# axiom_beta_smart_power_adapter_v0_1_r1_1.net
KiCad netlist of a schematic drawn in EAGLE
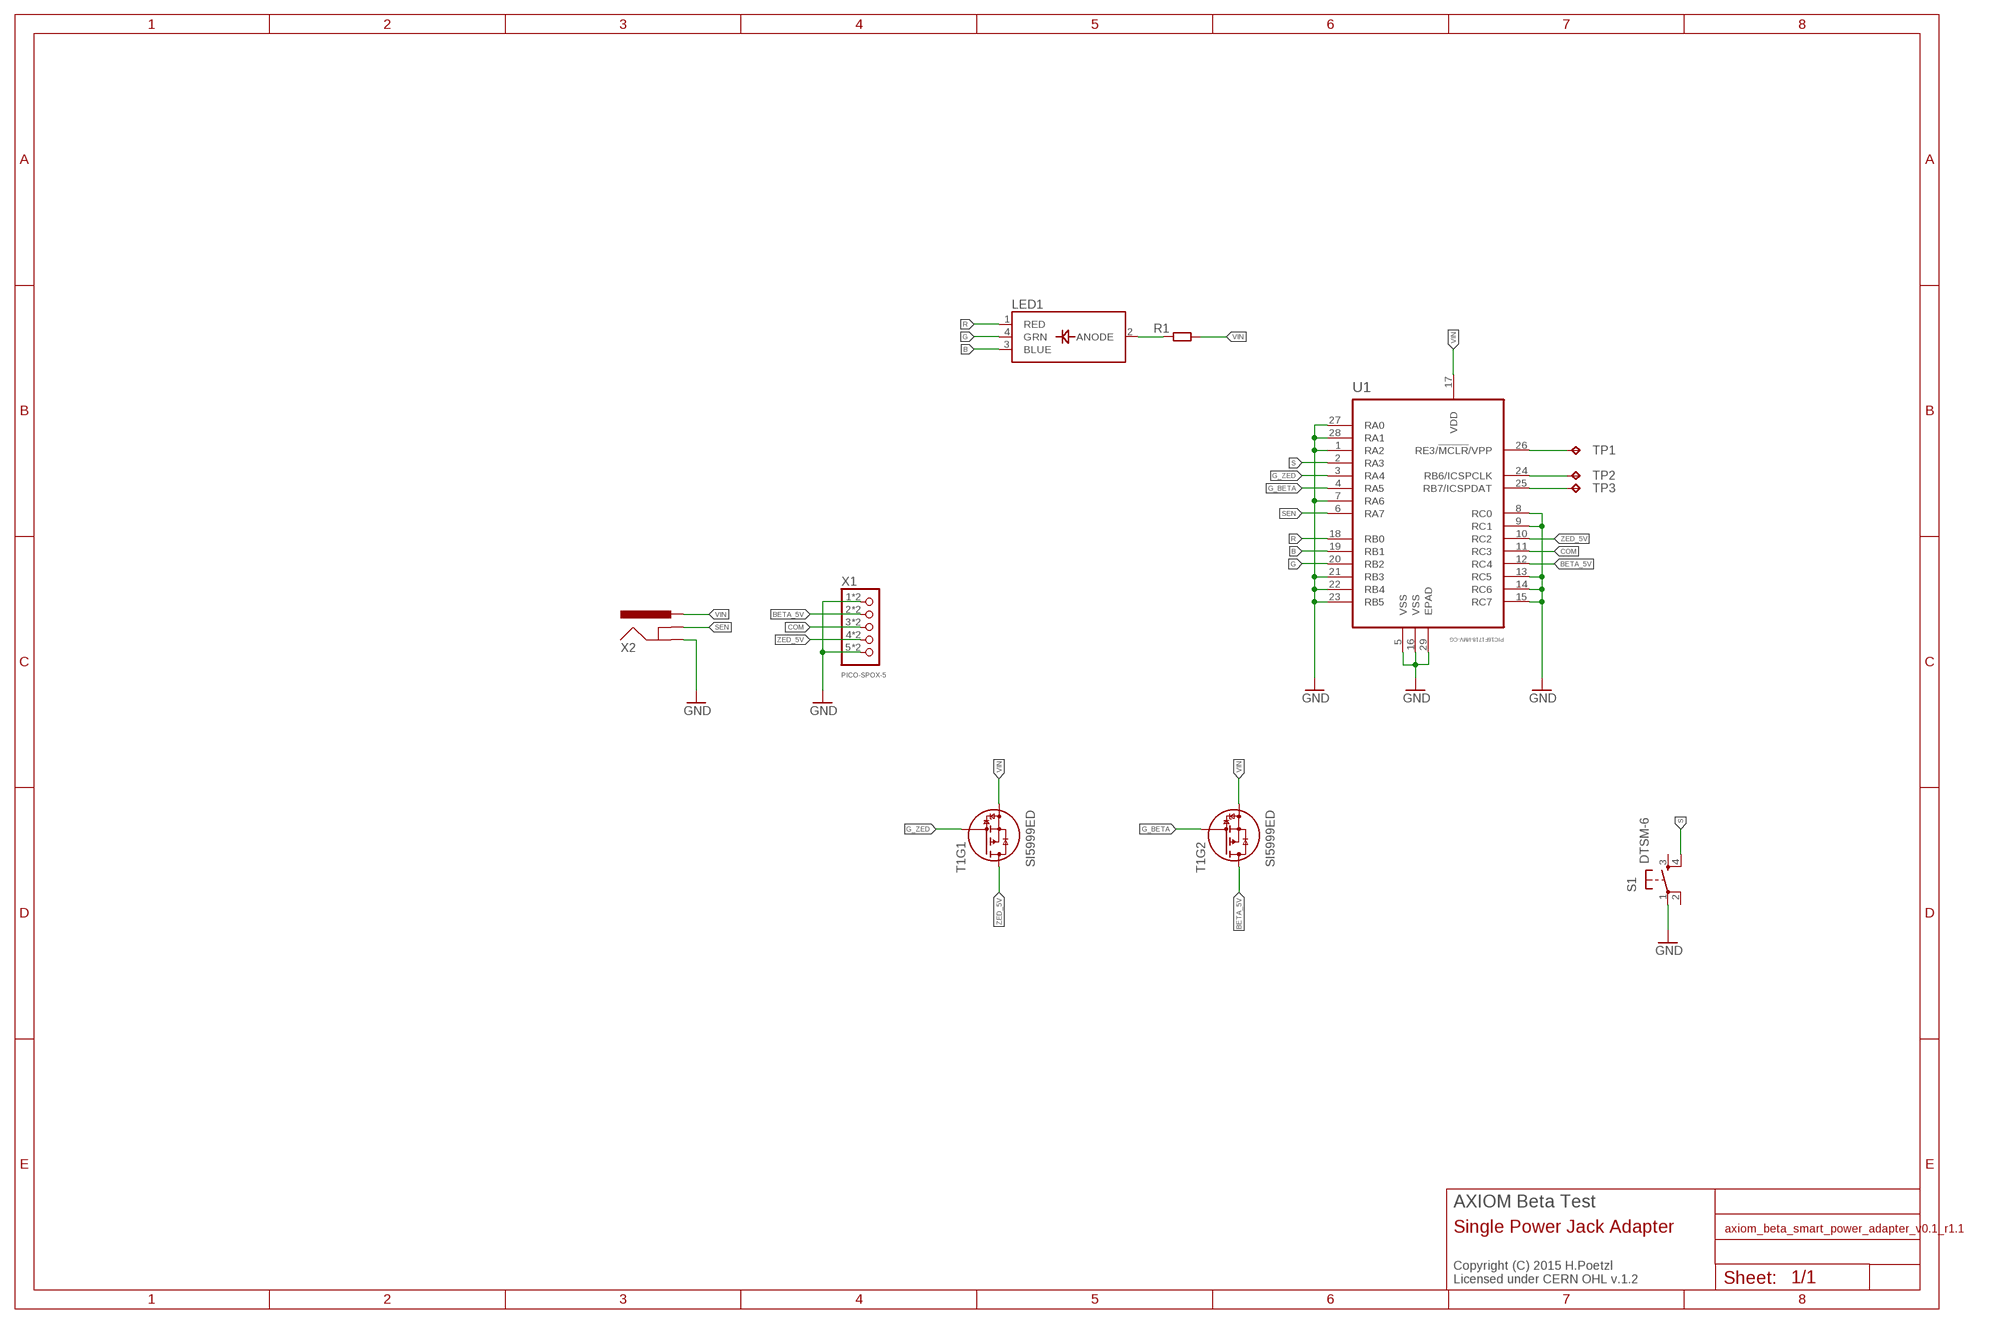
[diagram p0: schematic, sheet 1]

(export (version "E")
  (design (tool "Eeschema 10.0.6"))
  (components
    (comp (ref "LED1")
      (value "LED_RGB_PLCC4")
      (footprint "eagle-import:RGBLED_PLCC4")
      (libsource (lib "eagle-import") (part "LED_RGB_PLCC4"))
    )
    (comp (ref "R1")
      (value "R0402-C")
      (footprint "eagle-import:0402-C")
      (libsource (lib "eagle-import") (part "R0402-C"))
    )
    (comp (ref "S1")
      (value "DTSM-6")
      (footprint "eagle-import:3X4MM")
      (libsource (lib "eagle-import") (part "DTSM-6"))
    )
    (comp (ref "T1")
      (value "SI5999ED")
      (footprint "eagle-import:PPAK-CHIPFET-DUAL")
      (libsource (lib "eagle-import") (part "SI5999ED"))
    )
    (comp (ref "TP1")
      (value "TPTP07R")
      (footprint "eagle-import:TP07R")
      (libsource (lib "eagle-import") (part "TPTP07R"))
    )
    (comp (ref "TP2")
      (value "TPTP07R")
      (footprint "eagle-import:TP07R")
      (libsource (lib "eagle-import") (part "TPTP07R"))
    )
    (comp (ref "TP3")
      (value "TPTP07R")
      (footprint "eagle-import:TP07R")
      (libsource (lib "eagle-import") (part "TPTP07R"))
    )
    (comp (ref "U1")
      (value "PIC16F1718-I/MV-CG")
      (footprint "eagle-import:QFN40P400X400X55-29N-CGND")
      (libsource (lib "eagle-import") (part "PIC16F1718-I/MV-CG"))
    )
    (comp (ref "X1")
      (value "PICO-SPOX-5")
      (footprint "eagle-import:PICO-SPOX-5")
      (libsource (lib "eagle-import") (part "PICO-SPOX-5"))
    )
    (comp (ref "X2")
      (value "POWER_JACKPTH_SLOT")
      (footprint "eagle-import:POWER_JACK_PTH_SLOT")
      (libsource (lib "eagle-import") (part "POWER_JACKPTH_SLOT"))
    )
  )
  (nets
    (net (code "1") (name "B") (class "Default")
      (node (ref "LED1") (pin "3") (pinfunction "BLUE_3") (pintype "bidirectional"))
      (node (ref "U1") (pin "19") (pinfunction "RB1_19") (pintype "bidirectional"))
    )
    (net (code "2") (name "BETA_5V") (class "Default")
      (node (ref "T1") (pin "5") (pinfunction "D_5") (pintype "passive"))
      (node (ref "T1") (pin "6") (pinfunction "D_6") (pintype "passive"))
      (node (ref "T1") (pin "EP56") (pinfunction "D_EP56") (pintype "passive"))
      (node (ref "U1") (pin "12") (pinfunction "RC4_12") (pintype "bidirectional"))
      (node (ref "X1") (pin "2") (pinfunction "2_2") (pintype "passive"))
      (node (ref "X1") (pin "2A") (pinfunction "2_2A") (pintype "passive"))
    )
    (net (code "3") (name "COM") (class "Default")
      (node (ref "U1") (pin "11") (pinfunction "RC3_11") (pintype "bidirectional"))
      (node (ref "X1") (pin "3") (pinfunction "3_3") (pintype "passive"))
      (node (ref "X1") (pin "3A") (pinfunction "3_3A") (pintype "passive"))
    )
    (net (code "4") (name "G") (class "Default")
      (node (ref "LED1") (pin "4") (pinfunction "GRN_4") (pintype "bidirectional"))
      (node (ref "U1") (pin "20") (pinfunction "RB2_20") (pintype "bidirectional"))
    )
    (net (code "5") (name "GND") (class "Default")
      (node (ref "S1") (pin "1") (pinfunction "1_1") (pintype "passive"))
      (node (ref "U1") (pin "1") (pinfunction "RA2_1") (pintype "bidirectional"))
      (node (ref "U1") (pin "13") (pinfunction "RC5_13") (pintype "bidirectional"))
      (node (ref "U1") (pin "14") (pinfunction "RC6_14") (pintype "bidirectional"))
      (node (ref "U1") (pin "15") (pinfunction "RC7_15") (pintype "bidirectional"))
      (node (ref "U1") (pin "16") (pinfunction "VSS_16") (pintype "power_in"))
      (node (ref "U1") (pin "21") (pinfunction "RB3_21") (pintype "bidirectional"))
      (node (ref "U1") (pin "22") (pinfunction "RB4_22") (pintype "bidirectional"))
      (node (ref "U1") (pin "23") (pinfunction "RB5_23") (pintype "bidirectional"))
      (node (ref "U1") (pin "27") (pinfunction "RA0_27") (pintype "bidirectional"))
      (node (ref "U1") (pin "28") (pinfunction "RA1_28") (pintype "bidirectional"))
      (node (ref "U1") (pin "29") (pinfunction "EPAD_29") (pintype "passive"))
      (node (ref "U1") (pin "5") (pinfunction "VSS_5") (pintype "power_in"))
      (node (ref "U1") (pin "7") (pinfunction "RA6_7") (pintype "bidirectional"))
      (node (ref "U1") (pin "8") (pinfunction "RC0_8") (pintype "bidirectional"))
      (node (ref "U1") (pin "9") (pinfunction "RC1_9") (pintype "bidirectional"))
      (node (ref "X1") (pin "1") (pinfunction "1_1") (pintype "passive"))
      (node (ref "X1") (pin "1A") (pinfunction "1_1A") (pintype "passive"))
      (node (ref "X1") (pin "5") (pinfunction "5_5") (pintype "passive"))
      (node (ref "X1") (pin "5A") (pinfunction "5_5A") (pintype "passive"))
      (node (ref "X2") (pin "GND") (pinfunction "GND_GND") (pintype "bidirectional"))
    )
    (net (code "6") (name "G_BETA") (class "Default")
      (node (ref "T1") (pin "4") (pinfunction "G_4") (pintype "passive"))
      (node (ref "U1") (pin "4") (pinfunction "RA5_4") (pintype "bidirectional"))
    )
    (net (code "7") (name "G_ZED") (class "Default")
      (node (ref "T1") (pin "2") (pinfunction "G_2") (pintype "passive"))
      (node (ref "U1") (pin "3") (pinfunction "RA4_3") (pintype "bidirectional"))
    )
    (net (code "8") (name "Net-(LED1-ANODE)") (class "Default")
      (node (ref "LED1") (pin "2") (pinfunction "ANODE_2") (pintype "power_in"))
      (node (ref "R1") (pin "1") (pinfunction "1_1") (pintype "passive"))
    )
    (net (code "9") (name "Net-(U1-RB6{slash}ICSPCLK)") (class "Default")
      (node (ref "TP2") (pin "TP") (pinfunction "TP_TP") (pintype "input"))
      (node (ref "U1") (pin "24") (pinfunction "RB6/ICSPCLK_24") (pintype "bidirectional"))
    )
    (net (code "10") (name "Net-(U1-RB7{slash}ICSPDAT)") (class "Default")
      (node (ref "TP3") (pin "TP") (pinfunction "TP_TP") (pintype "input"))
      (node (ref "U1") (pin "25") (pinfunction "RB7/ICSPDAT_25") (pintype "bidirectional"))
    )
    (net (code "11") (name "Net-(U1-RE3{slash}~{MCLR}{slash}VPP)") (class "Default")
      (node (ref "TP1") (pin "TP") (pinfunction "TP_TP") (pintype "input"))
      (node (ref "U1") (pin "26") (pinfunction "RE3/~{MCLR}/VPP_26") (pintype "bidirectional"))
    )
    (net (code "12") (name "R") (class "Default")
      (node (ref "LED1") (pin "1") (pinfunction "RED_1") (pintype "bidirectional"))
      (node (ref "U1") (pin "18") (pinfunction "RB0_18") (pintype "bidirectional"))
    )
    (net (code "13") (name "S") (class "Default")
      (node (ref "S1") (pin "4") (pinfunction "4_4") (pintype "passive"))
      (node (ref "U1") (pin "2") (pinfunction "RA3_2") (pintype "bidirectional"))
    )
    (net (code "14") (name "SEN") (class "Default")
      (node (ref "U1") (pin "6") (pinfunction "RA7_6") (pintype "bidirectional"))
      (node (ref "X2") (pin "SHUNT") (pinfunction "GNDBREAK_SHUNT") (pintype "bidirectional"))
    )
    (net (code "15") (name "VIN") (class "Default")
      (node (ref "R1") (pin "2") (pinfunction "2_2") (pintype "passive"))
      (node (ref "T1") (pin "1") (pinfunction "S_1") (pintype "passive"))
      (node (ref "T1") (pin "3") (pinfunction "S_3") (pintype "passive"))
      (node (ref "U1") (pin "17") (pinfunction "VDD_17") (pintype "power_in"))
      (node (ref "X2") (pin "PWR") (pinfunction "PWR_PWR") (pintype "bidirectional"))
    )
    (net (code "16") (name "ZED_5V") (class "Default")
      (node (ref "T1") (pin "7") (pinfunction "D_7") (pintype "passive"))
      (node (ref "T1") (pin "8") (pinfunction "D_8") (pintype "passive"))
      (node (ref "T1") (pin "EP78") (pinfunction "D_EP78") (pintype "passive"))
      (node (ref "U1") (pin "10") (pinfunction "RC2_10") (pintype "bidirectional"))
      (node (ref "X1") (pin "4") (pinfunction "4_4") (pintype "passive"))
      (node (ref "X1") (pin "4A") (pinfunction "4_4A") (pintype "passive"))
    )
    (net (code "17") (name "unconnected-(S1-Pad2)") (class "Default")
      (node (ref "S1") (pin "2") (pinfunction "2_2") (pintype "passive"))
    )
    (net (code "18") (name "unconnected-(S1-Pad3)") (class "Default")
      (node (ref "S1") (pin "3") (pinfunction "3_3") (pintype "passive"))
    )
  )
)
